# R613B.net
KiCad netlist of a schematic drawn in EAGLE
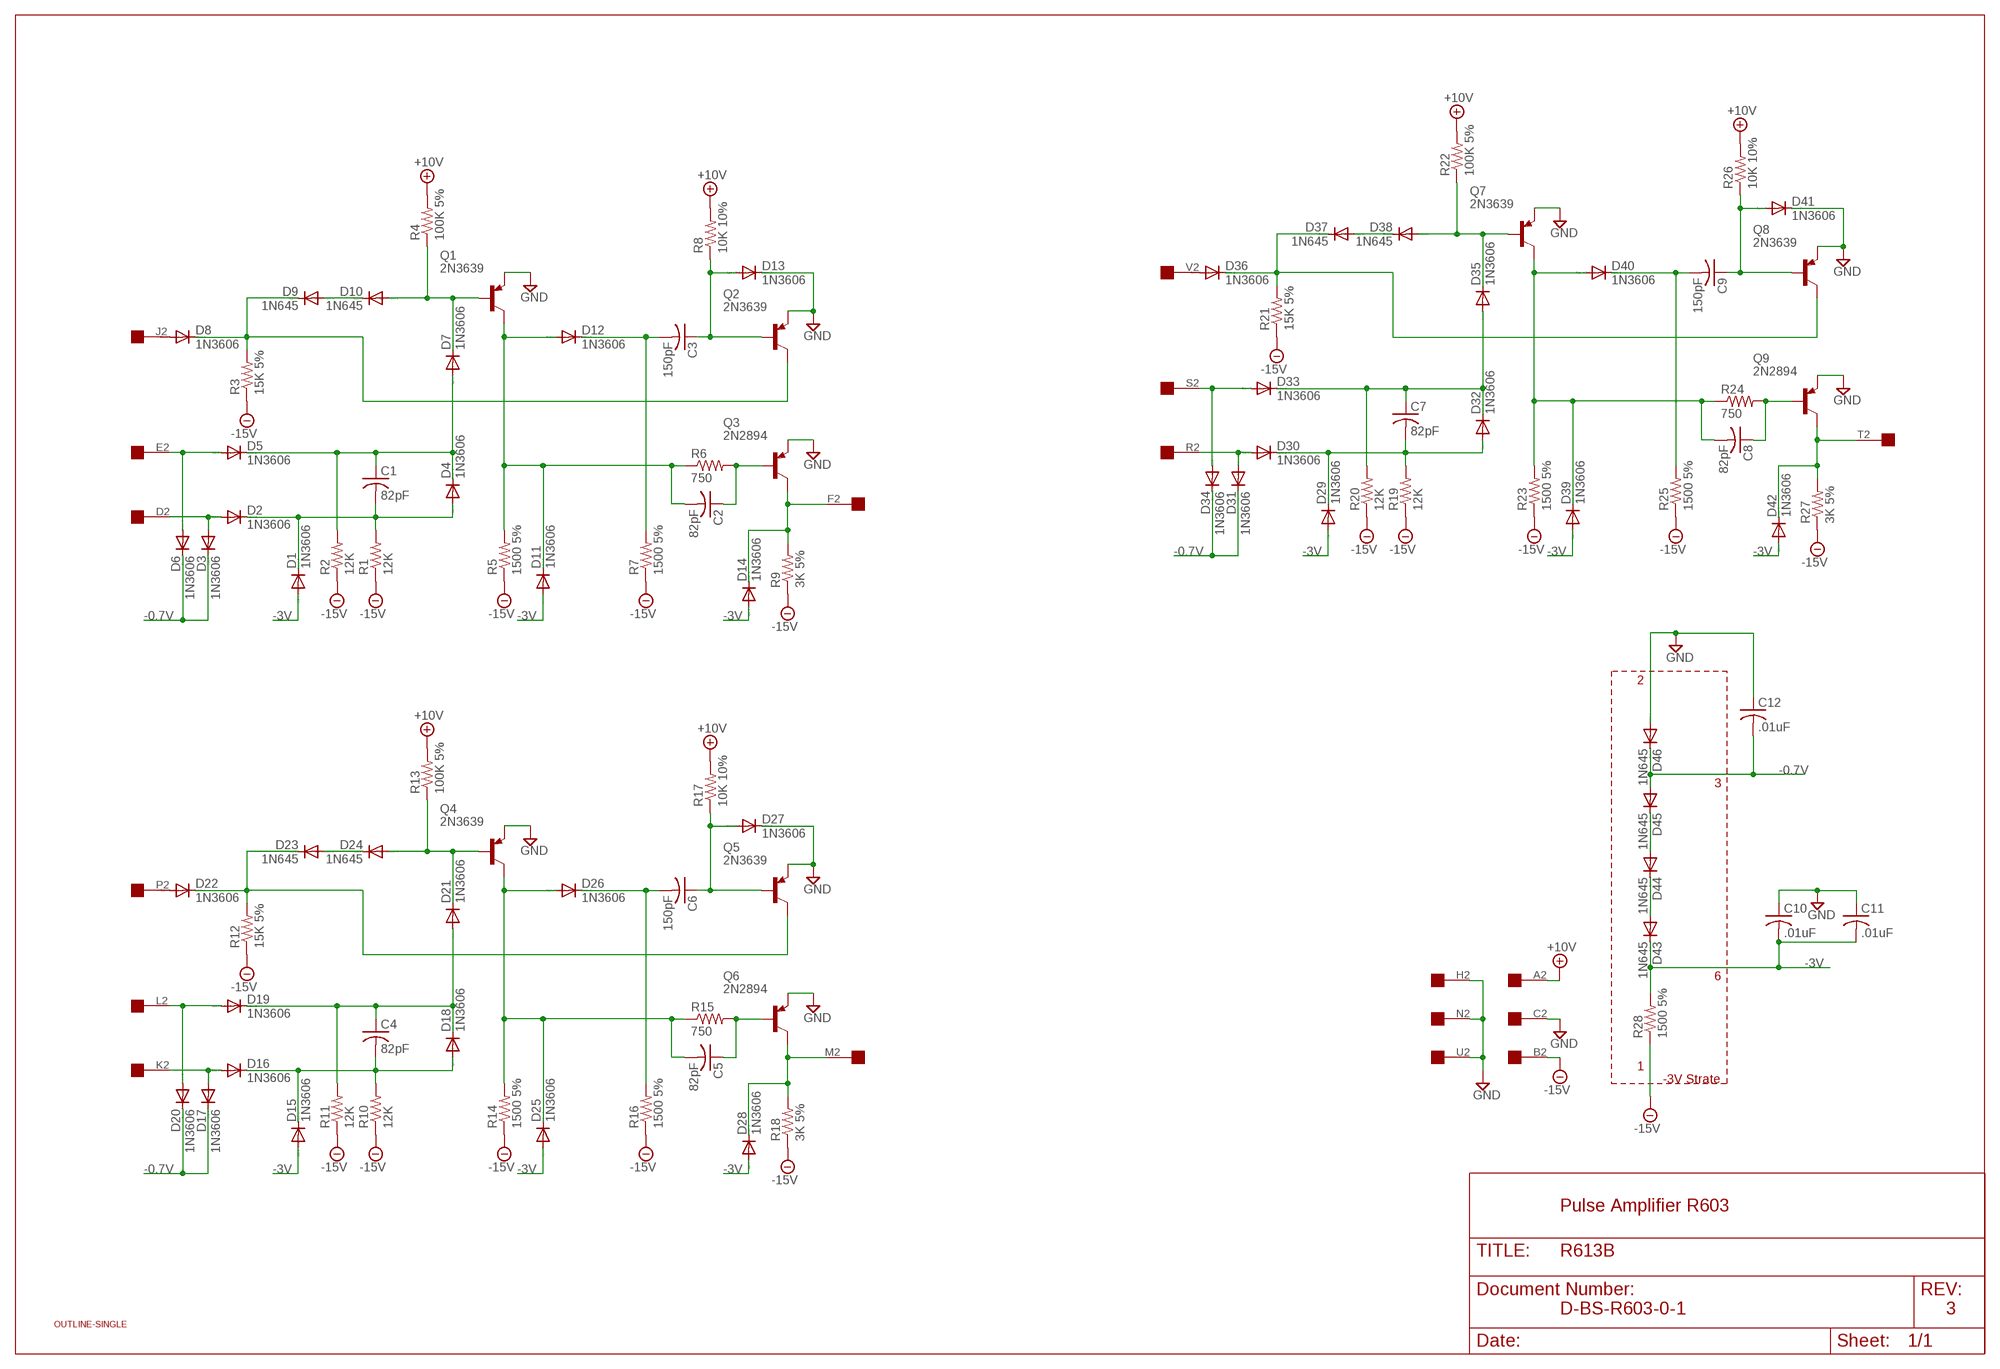
[diagram p0: schematic, sheet 1]

(export (version "E")
  (design (tool "Eeschema 10.0.6"))
  (components
    (comp (ref "C1")
      (value "82pF")
      (footprint "eagle-import:C050-025X075")
      (libsource (lib "eagle-import") (part "C-US050-025X075"))
    )
    (comp (ref "C2")
      (value "82pF")
      (footprint "eagle-import:C050-025X075")
      (libsource (lib "eagle-import") (part "C-US050-025X075"))
    )
    (comp (ref "C3")
      (value "150pF")
      (footprint "eagle-import:C050-025X075")
      (libsource (lib "eagle-import") (part "C-US050-025X075"))
    )
    (comp (ref "C4")
      (value "82pF")
      (footprint "eagle-import:C050-025X075")
      (libsource (lib "eagle-import") (part "C-US050-025X075"))
    )
    (comp (ref "C5")
      (value "82pF")
      (footprint "eagle-import:C050-025X075")
      (libsource (lib "eagle-import") (part "C-US050-025X075"))
    )
    (comp (ref "C6")
      (value "150pF")
      (footprint "eagle-import:C050-025X075")
      (libsource (lib "eagle-import") (part "C-US050-025X075"))
    )
    (comp (ref "C7")
      (value "82pF")
      (footprint "eagle-import:C050-025X075")
      (libsource (lib "eagle-import") (part "C-US050-025X075"))
    )
    (comp (ref "C8")
      (value "82pF")
      (footprint "eagle-import:C050-025X075")
      (libsource (lib "eagle-import") (part "C-US050-025X075"))
    )
    (comp (ref "C9")
      (value "150pF")
      (footprint "eagle-import:C050-025X075")
      (libsource (lib "eagle-import") (part "C-US050-025X075"))
    )
    (comp (ref "C10")
      (value ".01uF")
      (footprint "eagle-import:C050-025X075")
      (libsource (lib "eagle-import") (part "C-US050-025X075"))
    )
    (comp (ref "C11")
      (value ".01uF")
      (footprint "eagle-import:C050-025X075")
      (libsource (lib "eagle-import") (part "C-US050-025X075"))
    )
    (comp (ref "C12")
      (value ".01uF")
      (footprint "eagle-import:C050-025X075")
      (libsource (lib "eagle-import") (part "C-US050-025X075"))
    )
    (comp (ref "D1")
      (value "1N3606")
      (footprint "eagle-import:DO35-10")
      (libsource (lib "eagle-import") (part "1N4148DO35-10"))
    )
    (comp (ref "D2")
      (value "1N3606")
      (footprint "eagle-import:DO35-10")
      (libsource (lib "eagle-import") (part "1N4148DO35-10"))
    )
    (comp (ref "D3")
      (value "1N3606")
      (footprint "eagle-import:DO35-10")
      (libsource (lib "eagle-import") (part "1N4148DO35-10"))
    )
    (comp (ref "D4")
      (value "1N3606")
      (footprint "eagle-import:DO35-10")
      (libsource (lib "eagle-import") (part "1N4148DO35-10"))
    )
    (comp (ref "D5")
      (value "1N3606")
      (footprint "eagle-import:DO35-10")
      (libsource (lib "eagle-import") (part "1N4148DO35-10"))
    )
    (comp (ref "D6")
      (value "1N3606")
      (footprint "eagle-import:DO35-10")
      (libsource (lib "eagle-import") (part "1N4148DO35-10"))
    )
    (comp (ref "D7")
      (value "1N3606")
      (footprint "eagle-import:DO35-10")
      (libsource (lib "eagle-import") (part "1N4148DO35-10"))
    )
    (comp (ref "D8")
      (value "1N3606")
      (footprint "eagle-import:DO35-10")
      (libsource (lib "eagle-import") (part "1N4148DO35-10"))
    )
    (comp (ref "D9")
      (value "1N645")
      (footprint "eagle-import:DO35-10")
      (libsource (lib "eagle-import") (part "1N4148DO35-10"))
    )
    (comp (ref "D10")
      (value "1N645")
      (footprint "eagle-import:DO35-10")
      (libsource (lib "eagle-import") (part "1N4148DO35-10"))
    )
    (comp (ref "D11")
      (value "1N3606")
      (footprint "eagle-import:DO35-10")
      (libsource (lib "eagle-import") (part "1N4148DO35-10"))
    )
    (comp (ref "D12")
      (value "1N3606")
      (footprint "eagle-import:DO35-10")
      (libsource (lib "eagle-import") (part "1N4148DO35-10"))
    )
    (comp (ref "D13")
      (value "1N3606")
      (footprint "eagle-import:DO35-10")
      (libsource (lib "eagle-import") (part "1N4148DO35-10"))
    )
    (comp (ref "D14")
      (value "1N3606")
      (footprint "eagle-import:DO35-10")
      (libsource (lib "eagle-import") (part "1N4148DO35-10"))
    )
    (comp (ref "D15")
      (value "1N3606")
      (footprint "eagle-import:DO35-10")
      (libsource (lib "eagle-import") (part "1N4148DO35-10"))
    )
    (comp (ref "D16")
      (value "1N3606")
      (footprint "eagle-import:DO35-10")
      (libsource (lib "eagle-import") (part "1N4148DO35-10"))
    )
    (comp (ref "D17")
      (value "1N3606")
      (footprint "eagle-import:DO35-10")
      (libsource (lib "eagle-import") (part "1N4148DO35-10"))
    )
    (comp (ref "D18")
      (value "1N3606")
      (footprint "eagle-import:DO35-10")
      (libsource (lib "eagle-import") (part "1N4148DO35-10"))
    )
    (comp (ref "D19")
      (value "1N3606")
      (footprint "eagle-import:DO35-10")
      (libsource (lib "eagle-import") (part "1N4148DO35-10"))
    )
    (comp (ref "D20")
      (value "1N3606")
      (footprint "eagle-import:DO35-10")
      (libsource (lib "eagle-import") (part "1N4148DO35-10"))
    )
    (comp (ref "D21")
      (value "1N3606")
      (footprint "eagle-import:DO35-10")
      (libsource (lib "eagle-import") (part "1N4148DO35-10"))
    )
    (comp (ref "D22")
      (value "1N3606")
      (footprint "eagle-import:DO35-10")
      (libsource (lib "eagle-import") (part "1N4148DO35-10"))
    )
    (comp (ref "D23")
      (value "1N645")
      (footprint "eagle-import:DO35-10")
      (libsource (lib "eagle-import") (part "1N4148DO35-10"))
    )
    (comp (ref "D24")
      (value "1N645")
      (footprint "eagle-import:DO35-10")
      (libsource (lib "eagle-import") (part "1N4148DO35-10"))
    )
    (comp (ref "D25")
      (value "1N3606")
      (footprint "eagle-import:DO35-10")
      (libsource (lib "eagle-import") (part "1N4148DO35-10"))
    )
    (comp (ref "D26")
      (value "1N3606")
      (footprint "eagle-import:DO35-10")
      (libsource (lib "eagle-import") (part "1N4148DO35-10"))
    )
    (comp (ref "D27")
      (value "1N3606")
      (footprint "eagle-import:DO35-10")
      (libsource (lib "eagle-import") (part "1N4148DO35-10"))
    )
    (comp (ref "D28")
      (value "1N3606")
      (footprint "eagle-import:DO35-10")
      (libsource (lib "eagle-import") (part "1N4148DO35-10"))
    )
    (comp (ref "D29")
      (value "1N3606")
      (footprint "eagle-import:DO35-10")
      (libsource (lib "eagle-import") (part "1N4148DO35-10"))
    )
    (comp (ref "D30")
      (value "1N3606")
      (footprint "eagle-import:DO35-10")
      (libsource (lib "eagle-import") (part "1N4148DO35-10"))
    )
    (comp (ref "D31")
      (value "1N3606")
      (footprint "eagle-import:DO35-10")
      (libsource (lib "eagle-import") (part "1N4148DO35-10"))
    )
    (comp (ref "D32")
      (value "1N3606")
      (footprint "eagle-import:DO35-10")
      (libsource (lib "eagle-import") (part "1N4148DO35-10"))
    )
    (comp (ref "D33")
      (value "1N3606")
      (footprint "eagle-import:DO35-10")
      (libsource (lib "eagle-import") (part "1N4148DO35-10"))
    )
    (comp (ref "D34")
      (value "1N3606")
      (footprint "eagle-import:DO35-10")
      (libsource (lib "eagle-import") (part "1N4148DO35-10"))
    )
    (comp (ref "D35")
      (value "1N3606")
      (footprint "eagle-import:DO35-10")
      (libsource (lib "eagle-import") (part "1N4148DO35-10"))
    )
    (comp (ref "D36")
      (value "1N3606")
      (footprint "eagle-import:DO35-10")
      (libsource (lib "eagle-import") (part "1N4148DO35-10"))
    )
    (comp (ref "D37")
      (value "1N645")
      (footprint "eagle-import:DO35-10")
      (libsource (lib "eagle-import") (part "1N4148DO35-10"))
    )
    (comp (ref "D38")
      (value "1N645")
      (footprint "eagle-import:DO35-10")
      (libsource (lib "eagle-import") (part "1N4148DO35-10"))
    )
    (comp (ref "D39")
      (value "1N3606")
      (footprint "eagle-import:DO35-10")
      (libsource (lib "eagle-import") (part "1N4148DO35-10"))
    )
    (comp (ref "D40")
      (value "1N3606")
      (footprint "eagle-import:DO35-10")
      (libsource (lib "eagle-import") (part "1N4148DO35-10"))
    )
    (comp (ref "D41")
      (value "1N3606")
      (footprint "eagle-import:DO35-10")
      (libsource (lib "eagle-import") (part "1N4148DO35-10"))
    )
    (comp (ref "D42")
      (value "1N3606")
      (footprint "eagle-import:DO35-10")
      (libsource (lib "eagle-import") (part "1N4148DO35-10"))
    )
    (comp (ref "D43")
      (value "1N645")
      (footprint "eagle-import:DO35-10")
      (libsource (lib "eagle-import") (part "1N4148DO35-10"))
    )
    (comp (ref "D44")
      (value "1N645")
      (footprint "eagle-import:DO35-10")
      (libsource (lib "eagle-import") (part "1N4148DO35-10"))
    )
    (comp (ref "D45")
      (value "1N645")
      (footprint "eagle-import:DO35-10")
      (libsource (lib "eagle-import") (part "1N4148DO35-10"))
    )
    (comp (ref "D46")
      (value "1N645")
      (footprint "eagle-import:DO35-10")
      (libsource (lib "eagle-import") (part "1N4148DO35-10"))
    )
    (comp (ref "Q1")
      (value "2N3639")
      (footprint "eagle-import:TO39")
      (libsource (lib "eagle-import") (part "2N2904"))
    )
    (comp (ref "Q2")
      (value "2N3639")
      (footprint "eagle-import:TO39")
      (libsource (lib "eagle-import") (part "2N2904"))
    )
    (comp (ref "Q3")
      (value "2N2894")
      (footprint "eagle-import:TO39")
      (libsource (lib "eagle-import") (part "2N2904"))
    )
    (comp (ref "Q4")
      (value "2N3639")
      (footprint "eagle-import:TO39")
      (libsource (lib "eagle-import") (part "2N2904"))
    )
    (comp (ref "Q5")
      (value "2N3639")
      (footprint "eagle-import:TO39")
      (libsource (lib "eagle-import") (part "2N2904"))
    )
    (comp (ref "Q6")
      (value "2N2894")
      (footprint "eagle-import:TO39")
      (libsource (lib "eagle-import") (part "2N2904"))
    )
    (comp (ref "Q7")
      (value "2N3639")
      (footprint "eagle-import:TO39")
      (libsource (lib "eagle-import") (part "2N2904"))
    )
    (comp (ref "Q8")
      (value "2N3639")
      (footprint "eagle-import:TO39")
      (libsource (lib "eagle-import") (part "2N2904"))
    )
    (comp (ref "Q9")
      (value "2N2894")
      (footprint "eagle-import:TO39")
      (libsource (lib "eagle-import") (part "2N2904"))
    )
    (comp (ref "R1")
      (value "12K")
      (footprint "eagle-import:0207_10")
      (libsource (lib "eagle-import") (part "R-US_0207/10"))
    )
    (comp (ref "R2")
      (value "12K")
      (footprint "eagle-import:0207_10")
      (libsource (lib "eagle-import") (part "R-US_0207/10"))
    )
    (comp (ref "R3")
      (value "15K 5%")
      (footprint "eagle-import:0207_10")
      (libsource (lib "eagle-import") (part "R-US_0207/10"))
    )
    (comp (ref "R4")
      (value "100K 5%")
      (footprint "eagle-import:0207_10")
      (libsource (lib "eagle-import") (part "R-US_0207/10"))
    )
    (comp (ref "R5")
      (value "1500 5%")
      (footprint "eagle-import:0207_10")
      (libsource (lib "eagle-import") (part "R-US_0207/10"))
    )
    (comp (ref "R6")
      (value "750")
      (footprint "eagle-import:0207_10")
      (libsource (lib "eagle-import") (part "R-US_0207/10"))
    )
    (comp (ref "R7")
      (value "1500 5%")
      (footprint "eagle-import:0207_10")
      (libsource (lib "eagle-import") (part "R-US_0207/10"))
    )
    (comp (ref "R8")
      (value "10K 10%")
      (footprint "eagle-import:0207_10")
      (libsource (lib "eagle-import") (part "R-US_0207/10"))
    )
    (comp (ref "R9")
      (value "3K 5%")
      (footprint "eagle-import:0207_10")
      (libsource (lib "eagle-import") (part "R-US_0207/10"))
    )
    (comp (ref "R10")
      (value "12K")
      (footprint "eagle-import:0207_10")
      (libsource (lib "eagle-import") (part "R-US_0207/10"))
    )
    (comp (ref "R11")
      (value "12K")
      (footprint "eagle-import:0207_10")
      (libsource (lib "eagle-import") (part "R-US_0207/10"))
    )
    (comp (ref "R12")
      (value "15K 5%")
      (footprint "eagle-import:0207_10")
      (libsource (lib "eagle-import") (part "R-US_0207/10"))
    )
    (comp (ref "R13")
      (value "100K 5%")
      (footprint "eagle-import:0207_10")
      (libsource (lib "eagle-import") (part "R-US_0207/10"))
    )
    (comp (ref "R14")
      (value "1500 5%")
      (footprint "eagle-import:0207_10")
      (libsource (lib "eagle-import") (part "R-US_0207/10"))
    )
    (comp (ref "R15")
      (value "750")
      (footprint "eagle-import:0207_10")
      (libsource (lib "eagle-import") (part "R-US_0207/10"))
    )
    (comp (ref "R16")
      (value "1500 5%")
      (footprint "eagle-import:0207_10")
      (libsource (lib "eagle-import") (part "R-US_0207/10"))
    )
    (comp (ref "R17")
      (value "10K 10%")
      (footprint "eagle-import:0207_10")
      (libsource (lib "eagle-import") (part "R-US_0207/10"))
    )
    (comp (ref "R18")
      (value "3K 5%")
      (footprint "eagle-import:0207_10")
      (libsource (lib "eagle-import") (part "R-US_0207/10"))
    )
    (comp (ref "R19")
      (value "12K")
      (footprint "eagle-import:0207_10")
      (libsource (lib "eagle-import") (part "R-US_0207/10"))
    )
    (comp (ref "R20")
      (value "12K")
      (footprint "eagle-import:0207_10")
      (libsource (lib "eagle-import") (part "R-US_0207/10"))
    )
    (comp (ref "R21")
      (value "15K 5%")
      (footprint "eagle-import:0207_10")
      (libsource (lib "eagle-import") (part "R-US_0207/10"))
    )
    (comp (ref "R22")
      (value "100K 5%")
      (footprint "eagle-import:0207_10")
      (libsource (lib "eagle-import") (part "R-US_0207/10"))
    )
    (comp (ref "R23")
      (value "1500 5%")
      (footprint "eagle-import:0207_10")
      (libsource (lib "eagle-import") (part "R-US_0207/10"))
    )
    (comp (ref "R24")
      (value "750")
      (footprint "eagle-import:0207_10")
      (libsource (lib "eagle-import") (part "R-US_0207/10"))
    )
    (comp (ref "R25")
      (value "1500 5%")
      (footprint "eagle-import:0207_10")
      (libsource (lib "eagle-import") (part "R-US_0207/10"))
    )
    (comp (ref "R26")
      (value "10K 10%")
      (footprint "eagle-import:0207_10")
      (libsource (lib "eagle-import") (part "R-US_0207/10"))
    )
    (comp (ref "R27")
      (value "3K 5%")
      (footprint "eagle-import:0207_10")
      (libsource (lib "eagle-import") (part "R-US_0207/10"))
    )
    (comp (ref "R28")
      (value "1500 5%")
      (footprint "eagle-import:0207_10")
      (libsource (lib "eagle-import") (part "R-US_0207/10"))
    )
    (comp (ref "U$1")
      (value "OUTLINE-SINGLE")
      (footprint "eagle-import:SINGLE")
      (libsource (lib "eagle-import") (part "OUTLINE-SINGLE"))
    )
    (comp (ref "U$2")
      (value "EDGE-1")
      (footprint "eagle-import:EDGE-CON1")
      (libsource (lib "eagle-import") (part "EDGE-1"))
    )
  )
  (nets
    (net (code "1") (name "+10V") (class "Default")
      (node (ref "R13") (pin "2") (pinfunction "2_2") (pintype "passive"))
      (node (ref "R17") (pin "2") (pinfunction "2_2") (pintype "passive"))
      (node (ref "R22") (pin "2") (pinfunction "2_2") (pintype "passive"))
      (node (ref "R26") (pin "2") (pinfunction "2_2") (pintype "passive"))
      (node (ref "R4") (pin "2") (pinfunction "2_2") (pintype "passive"))
      (node (ref "R8") (pin "2") (pinfunction "2_2") (pintype "passive"))
      (node (ref "U$2") (pin "A2") (pinfunction "1_A2") (pintype "bidirectional"))
    )
    (net (code "2") (name "-15V") (class "Default")
      (node (ref "R1") (pin "1") (pinfunction "1_1") (pintype "passive"))
      (node (ref "R10") (pin "1") (pinfunction "1_1") (pintype "passive"))
      (node (ref "R11") (pin "1") (pinfunction "1_1") (pintype "passive"))
      (node (ref "R12") (pin "1") (pinfunction "1_1") (pintype "passive"))
      (node (ref "R14") (pin "1") (pinfunction "1_1") (pintype "passive"))
      (node (ref "R16") (pin "1") (pinfunction "1_1") (pintype "passive"))
      (node (ref "R18") (pin "1") (pinfunction "1_1") (pintype "passive"))
      (node (ref "R19") (pin "1") (pinfunction "1_1") (pintype "passive"))
      (node (ref "R2") (pin "1") (pinfunction "1_1") (pintype "passive"))
      (node (ref "R20") (pin "1") (pinfunction "1_1") (pintype "passive"))
      (node (ref "R21") (pin "1") (pinfunction "1_1") (pintype "passive"))
      (node (ref "R23") (pin "1") (pinfunction "1_1") (pintype "passive"))
      (node (ref "R25") (pin "1") (pinfunction "1_1") (pintype "passive"))
      (node (ref "R27") (pin "1") (pinfunction "1_1") (pintype "passive"))
      (node (ref "R28") (pin "1") (pinfunction "1_1") (pintype "passive"))
      (node (ref "R3") (pin "1") (pinfunction "1_1") (pintype "passive"))
      (node (ref "R5") (pin "1") (pinfunction "1_1") (pintype "passive"))
      (node (ref "R7") (pin "1") (pinfunction "1_1") (pintype "passive"))
      (node (ref "R9") (pin "1") (pinfunction "1_1") (pintype "passive"))
      (node (ref "U$2") (pin "B2") (pinfunction "1_B2") (pintype "bidirectional"))
    )
    (net (code "3") (name "/-0.7V") (class "Default")
      (node (ref "C12") (pin "2") (pinfunction "2_2") (pintype "passive"))
      (node (ref "D17") (pin "C") (pinfunction "C_C") (pintype "passive"))
      (node (ref "D20") (pin "C") (pinfunction "C_C") (pintype "passive"))
      (node (ref "D3") (pin "C") (pinfunction "C_C") (pintype "passive"))
      (node (ref "D31") (pin "C") (pinfunction "C_C") (pintype "passive"))
      (node (ref "D34") (pin "C") (pinfunction "C_C") (pintype "passive"))
      (node (ref "D45") (pin "A") (pinfunction "A_A") (pintype "passive"))
      (node (ref "D46") (pin "C") (pinfunction "C_C") (pintype "passive"))
      (node (ref "D6") (pin "C") (pinfunction "C_C") (pintype "passive"))
    )
    (net (code "4") (name "/-3V") (class "Default")
      (node (ref "C10") (pin "2") (pinfunction "2_2") (pintype "passive"))
      (node (ref "C11") (pin "2") (pinfunction "2_2") (pintype "passive"))
      (node (ref "D1") (pin "A") (pinfunction "A_A") (pintype "passive"))
      (node (ref "D11") (pin "A") (pinfunction "A_A") (pintype "passive"))
      (node (ref "D14") (pin "A") (pinfunction "A_A") (pintype "passive"))
      (node (ref "D15") (pin "A") (pinfunction "A_A") (pintype "passive"))
      (node (ref "D25") (pin "A") (pinfunction "A_A") (pintype "passive"))
      (node (ref "D28") (pin "A") (pinfunction "A_A") (pintype "passive"))
      (node (ref "D29") (pin "A") (pinfunction "A_A") (pintype "passive"))
      (node (ref "D39") (pin "A") (pinfunction "A_A") (pintype "passive"))
      (node (ref "D42") (pin "A") (pinfunction "A_A") (pintype "passive"))
      (node (ref "D43") (pin "C") (pinfunction "C_C") (pintype "passive"))
      (node (ref "R28") (pin "2") (pinfunction "2_2") (pintype "passive"))
    )
    (net (code "5") (name "GND") (class "Default")
      (node (ref "C10") (pin "1") (pinfunction "1_1") (pintype "passive"))
      (node (ref "C11") (pin "1") (pinfunction "1_1") (pintype "passive"))
      (node (ref "C12") (pin "1") (pinfunction "1_1") (pintype "passive"))
      (node (ref "D13") (pin "C") (pinfunction "C_C") (pintype "passive"))
      (node (ref "D27") (pin "C") (pinfunction "C_C") (pintype "passive"))
      (node (ref "D41") (pin "C") (pinfunction "C_C") (pintype "passive"))
      (node (ref "D46") (pin "A") (pinfunction "A_A") (pintype "passive"))
      (node (ref "Q1") (pin "1") (pinfunction "E_1") (pintype "passive"))
      (node (ref "Q2") (pin "1") (pinfunction "E_1") (pintype "passive"))
      (node (ref "Q3") (pin "1") (pinfunction "E_1") (pintype "passive"))
      (node (ref "Q4") (pin "1") (pinfunction "E_1") (pintype "passive"))
      (node (ref "Q5") (pin "1") (pinfunction "E_1") (pintype "passive"))
      (node (ref "Q6") (pin "1") (pinfunction "E_1") (pintype "passive"))
      (node (ref "Q7") (pin "1") (pinfunction "E_1") (pintype "passive"))
      (node (ref "Q8") (pin "1") (pinfunction "E_1") (pintype "passive"))
      (node (ref "Q9") (pin "1") (pinfunction "E_1") (pintype "passive"))
      (node (ref "U$2") (pin "C2") (pinfunction "1_C2") (pintype "bidirectional"))
      (node (ref "U$2") (pin "H2") (pinfunction "1_H2") (pintype "bidirectional"))
      (node (ref "U$2") (pin "N2") (pinfunction "1_N2") (pintype "bidirectional"))
      (node (ref "U$2") (pin "U2") (pinfunction "1_U2") (pintype "bidirectional"))
    )
    (net (code "6") (name "Net-(C1-Pad1)") (class "Default")
      (node (ref "C1") (pin "1") (pinfunction "1_1") (pintype "passive"))
      (node (ref "D4") (pin "C") (pinfunction "C_C") (pintype "passive"))
      (node (ref "D5") (pin "C") (pinfunction "C_C") (pintype "passive"))
      (node (ref "D7") (pin "A") (pinfunction "A_A") (pintype "passive"))
      (node (ref "R2") (pin "2") (pinfunction "2_2") (pintype "passive"))
    )
    (net (code "7") (name "Net-(C1-Pad2)") (class "Default")
      (node (ref "C1") (pin "2") (pinfunction "2_2") (pintype "passive"))
      (node (ref "D1") (pin "C") (pinfunction "C_C") (pintype "passive"))
      (node (ref "D2") (pin "C") (pinfunction "C_C") (pintype "passive"))
      (node (ref "D4") (pin "A") (pinfunction "A_A") (pintype "passive"))
      (node (ref "R1") (pin "2") (pinfunction "2_2") (pintype "passive"))
    )
    (net (code "8") (name "Net-(C3-Pad2)") (class "Default")
      (node (ref "C3") (pin "2") (pinfunction "2_2") (pintype "passive"))
      (node (ref "D12") (pin "C") (pinfunction "C_C") (pintype "passive"))
      (node (ref "R7") (pin "2") (pinfunction "2_2") (pintype "passive"))
    )
    (net (code "9") (name "Net-(C4-Pad1)") (class "Default")
      (node (ref "C4") (pin "1") (pinfunction "1_1") (pintype "passive"))
      (node (ref "D18") (pin "C") (pinfunction "C_C") (pintype "passive"))
      (node (ref "D19") (pin "C") (pinfunction "C_C") (pintype "passive"))
      (node (ref "D21") (pin "A") (pinfunction "A_A") (pintype "passive"))
      (node (ref "R11") (pin "2") (pinfunction "2_2") (pintype "passive"))
    )
    (net (code "10") (name "Net-(C4-Pad2)") (class "Default")
      (node (ref "C4") (pin "2") (pinfunction "2_2") (pintype "passive"))
      (node (ref "D15") (pin "C") (pinfunction "C_C") (pintype "passive"))
      (node (ref "D16") (pin "C") (pinfunction "C_C") (pintype "passive"))
      (node (ref "D18") (pin "A") (pinfunction "A_A") (pintype "passive"))
      (node (ref "R10") (pin "2") (pinfunction "2_2") (pintype "passive"))
    )
    (net (code "11") (name "Net-(C6-Pad2)") (class "Default")
      (node (ref "C6") (pin "2") (pinfunction "2_2") (pintype "passive"))
      (node (ref "D26") (pin "C") (pinfunction "C_C") (pintype "passive"))
      (node (ref "R16") (pin "2") (pinfunction "2_2") (pintype "passive"))
    )
    (net (code "12") (name "Net-(C7-Pad1)") (class "Default")
      (node (ref "C7") (pin "1") (pinfunction "1_1") (pintype "passive"))
      (node (ref "D32") (pin "C") (pinfunction "C_C") (pintype "passive"))
      (node (ref "D33") (pin "C") (pinfunction "C_C") (pintype "passive"))
      (node (ref "D35") (pin "A") (pinfunction "A_A") (pintype "passive"))
      (node (ref "R20") (pin "2") (pinfunction "2_2") (pintype "passive"))
    )
    (net (code "13") (name "Net-(C7-Pad2)") (class "Default")
      (node (ref "C7") (pin "2") (pinfunction "2_2") (pintype "passive"))
      (node (ref "D29") (pin "C") (pinfunction "C_C") (pintype "passive"))
      (node (ref "D30") (pin "C") (pinfunction "C_C") (pintype "passive"))
      (node (ref "D32") (pin "A") (pinfunction "A_A") (pintype "passive"))
      (node (ref "R19") (pin "2") (pinfunction "2_2") (pintype "passive"))
    )
    (net (code "14") (name "Net-(C9-Pad2)") (class "Default")
      (node (ref "C9") (pin "2") (pinfunction "2_2") (pintype "passive"))
      (node (ref "D40") (pin "C") (pinfunction "C_C") (pintype "passive"))
      (node (ref "R25") (pin "2") (pinfunction "2_2") (pintype "passive"))
    )
    (net (code "15") (name "Net-(D10-PadC)") (class "Default")
      (node (ref "D10") (pin "C") (pinfunction "C_C") (pintype "passive"))
      (node (ref "D9") (pin "A") (pinfunction "A_A") (pintype "passive"))
    )
    (net (code "16") (name "Net-(D23-PadA)") (class "Default")
      (node (ref "D23") (pin "A") (pinfunction "A_A") (pintype "passive"))
      (node (ref "D24") (pin "C") (pinfunction "C_C") (pintype "passive"))
    )
    (net (code "17") (name "Net-(D37-PadA)") (class "Default")
      (node (ref "D37") (pin "A") (pinfunction "A_A") (pintype "passive"))
      (node (ref "D38") (pin "C") (pinfunction "C_C") (pintype "passive"))
    )
    (net (code "18") (name "Net-(D43-PadA)") (class "Default")
      (node (ref "D43") (pin "A") (pinfunction "A_A") (pintype "passive"))
      (node (ref "D44") (pin "C") (pinfunction "C_C") (pintype "passive"))
    )
    (net (code "19") (name "Net-(D44-PadA)") (class "Default")
      (node (ref "D44") (pin "A") (pinfunction "A_A") (pintype "passive"))
      (node (ref "D45") (pin "C") (pinfunction "C_C") (pintype "passive"))
    )
    (net (code "20") (name "Net-(Q1-B)") (class "Default")
      (node (ref "D10") (pin "A") (pinfunction "A_A") (pintype "passive"))
      (node (ref "D7") (pin "C") (pinfunction "C_C") (pintype "passive"))
      (node (ref "Q1") (pin "2") (pinfunction "B_2") (pintype "passive"))
      (node (ref "R4") (pin "1") (pinfunction "1_1") (pintype "passive"))
    )
    (net (code "21") (name "Net-(Q1-C)") (class "Default")
      (node (ref "C2") (pin "2") (pinfunction "2_2") (pintype "passive"))
      (node (ref "D11") (pin "C") (pinfunction "C_C") (pintype "passive"))
      (node (ref "D12") (pin "A") (pinfunction "A_A") (pintype "passive"))
      (node (ref "Q1") (pin "3") (pinfunction "C_3") (pintype "passive"))
      (node (ref "R5") (pin "2") (pinfunction "2_2") (pintype "passive"))
      (node (ref "R6") (pin "1") (pinfunction "1_1") (pintype "passive"))
    )
    (net (code "22") (name "Net-(Q2-B)") (class "Default")
      (node (ref "C3") (pin "1") (pinfunction "1_1") (pintype "passive"))
      (node (ref "D13") (pin "A") (pinfunction "A_A") (pintype "passive"))
      (node (ref "Q2") (pin "2") (pinfunction "B_2") (pintype "passive"))
      (node (ref "R8") (pin "1") (pinfunction "1_1") (pintype "passive"))
    )
    (net (code "23") (name "Net-(Q2-C)") (class "Default")
      (node (ref "D8") (pin "C") (pinfunction "C_C") (pintype "passive"))
      (node (ref "D9") (pin "C") (pinfunction "C_C") (pintype "passive"))
      (node (ref "Q2") (pin "3") (pinfunction "C_3") (pintype "passive"))
      (node (ref "R3") (pin "2") (pinfunction "2_2") (pintype "passive"))
    )
    (net (code "24") (name "Net-(Q3-B)") (class "Default")
      (node (ref "C2") (pin "1") (pinfunction "1_1") (pintype "passive"))
      (node (ref "Q3") (pin "2") (pinfunction "B_2") (pintype "passive"))
      (node (ref "R6") (pin "2") (pinfunction "2_2") (pintype "passive"))
    )
    (net (code "25") (name "Net-(Q3-C)") (class "Default")
      (node (ref "D14") (pin "C") (pinfunction "C_C") (pintype "passive"))
      (node (ref "Q3") (pin "3") (pinfunction "C_3") (pintype "passive"))
      (node (ref "R9") (pin "2") (pinfunction "2_2") (pintype "passive"))
      (node (ref "U$2") (pin "F2") (pinfunction "1_F2") (pintype "bidirectional"))
    )
    (net (code "26") (name "Net-(Q4-B)") (class "Default")
      (node (ref "D21") (pin "C") (pinfunction "C_C") (pintype "passive"))
      (node (ref "D24") (pin "A") (pinfunction "A_A") (pintype "passive"))
      (node (ref "Q4") (pin "2") (pinfunction "B_2") (pintype "passive"))
      (node (ref "R13") (pin "1") (pinfunction "1_1") (pintype "passive"))
    )
    (net (code "27") (name "Net-(Q4-C)") (class "Default")
      (node (ref "C5") (pin "2") (pinfunction "2_2") (pintype "passive"))
      (node (ref "D25") (pin "C") (pinfunction "C_C") (pintype "passive"))
      (node (ref "D26") (pin "A") (pinfunction "A_A") (pintype "passive"))
      (node (ref "Q4") (pin "3") (pinfunction "C_3") (pintype "passive"))
      (node (ref "R14") (pin "2") (pinfunction "2_2") (pintype "passive"))
      (node (ref "R15") (pin "1") (pinfunction "1_1") (pintype "passive"))
    )
    (net (code "28") (name "Net-(Q5-B)") (class "Default")
      (node (ref "C6") (pin "1") (pinfunction "1_1") (pintype "passive"))
      (node (ref "D27") (pin "A") (pinfunction "A_A") (pintype "passive"))
      (node (ref "Q5") (pin "2") (pinfunction "B_2") (pintype "passive"))
      (node (ref "R17") (pin "1") (pinfunction "1_1") (pintype "passive"))
    )
    (net (code "29") (name "Net-(Q5-C)") (class "Default")
      (node (ref "D22") (pin "C") (pinfunction "C_C") (pintype "passive"))
      (node (ref "D23") (pin "C") (pinfunction "C_C") (pintype "passive"))
      (node (ref "Q5") (pin "3") (pinfunction "C_3") (pintype "passive"))
      (node (ref "R12") (pin "2") (pinfunction "2_2") (pintype "passive"))
    )
    (net (code "30") (name "Net-(Q6-B)") (class "Default")
      (node (ref "C5") (pin "1") (pinfunction "1_1") (pintype "passive"))
      (node (ref "Q6") (pin "2") (pinfunction "B_2") (pintype "passive"))
      (node (ref "R15") (pin "2") (pinfunction "2_2") (pintype "passive"))
    )
    (net (code "31") (name "Net-(Q6-C)") (class "Default")
      (node (ref "D28") (pin "C") (pinfunction "C_C") (pintype "passive"))
      (node (ref "Q6") (pin "3") (pinfunction "C_3") (pintype "passive"))
      (node (ref "R18") (pin "2") (pinfunction "2_2") (pintype "passive"))
      (node (ref "U$2") (pin "M2") (pinfunction "1_M2") (pintype "bidirectional"))
    )
    (net (code "32") (name "Net-(Q7-B)") (class "Default")
      (node (ref "D35") (pin "C") (pinfunction "C_C") (pintype "passive"))
      (node (ref "D38") (pin "A") (pinfunction "A_A") (pintype "passive"))
      (node (ref "Q7") (pin "2") (pinfunction "B_2") (pintype "passive"))
      (node (ref "R22") (pin "1") (pinfunction "1_1") (pintype "passive"))
    )
    (net (code "33") (name "Net-(Q7-C)") (class "Default")
      (node (ref "C8") (pin "2") (pinfunction "2_2") (pintype "passive"))
      (node (ref "D39") (pin "C") (pinfunction "C_C") (pintype "passive"))
      (node (ref "D40") (pin "A") (pinfunction "A_A") (pintype "passive"))
      (node (ref "Q7") (pin "3") (pinfunction "C_3") (pintype "passive"))
      (node (ref "R23") (pin "2") (pinfunction "2_2") (pintype "passive"))
      (node (ref "R24") (pin "1") (pinfunction "1_1") (pintype "passive"))
    )
    (net (code "34") (name "Net-(Q8-B)") (class "Default")
      (node (ref "C9") (pin "1") (pinfunction "1_1") (pintype "passive"))
      (node (ref "D41") (pin "A") (pinfunction "A_A") (pintype "passive"))
      (node (ref "Q8") (pin "2") (pinfunction "B_2") (pintype "passive"))
      (node (ref "R26") (pin "1") (pinfunction "1_1") (pintype "passive"))
    )
    (net (code "35") (name "Net-(Q8-C)") (class "Default")
      (node (ref "D36") (pin "C") (pinfunction "C_C") (pintype "passive"))
      (node (ref "D37") (pin "C") (pinfunction "C_C") (pintype "passive"))
      (node (ref "Q8") (pin "3") (pinfunction "C_3") (pintype "passive"))
      (node (ref "R21") (pin "2") (pinfunction "2_2") (pintype "passive"))
    )
    (net (code "36") (name "Net-(Q9-B)") (class "Default")
      (node (ref "C8") (pin "1") (pinfunction "1_1") (pintype "passive"))
      (node (ref "Q9") (pin "2") (pinfunction "B_2") (pintype "passive"))
      (node (ref "R24") (pin "2") (pinfunction "2_2") (pintype "passive"))
    )
    (net (code "37") (name "Net-(Q9-C)") (class "Default")
      (node (ref "D42") (pin "C") (pinfunction "C_C") (pintype "passive"))
      (node (ref "Q9") (pin "3") (pinfunction "C_3") (pintype "passive"))
      (node (ref "R27") (pin "2") (pinfunction "2_2") (pintype "passive"))
      (node (ref "U$2") (pin "T2") (pinfunction "1_T2") (pintype "bidirectional"))
    )
    (net (code "38") (name "Net-(U$2D-1)") (class "Default")
      (node (ref "D2") (pin "A") (pinfunction "A_A") (pintype "passive"))
      (node (ref "D3") (pin "A") (pinfunction "A_A") (pintype "passive"))
      (node (ref "U$2") (pin "D2") (pinfunction "1_D2") (pintype "bidirectional"))
    )
    (net (code "39") (name "Net-(U$2E-1)") (class "Default")
      (node (ref "D5") (pin "A") (pinfunction "A_A") (pintype "passive"))
      (node (ref "D6") (pin "A") (pinfunction "A_A") (pintype "passive"))
      (node (ref "U$2") (pin "E2") (pinfunction "1_E2") (pintype "bidirectional"))
    )
    (net (code "40") (name "Net-(U$2H-1)") (class "Default")
      (node (ref "D8") (pin "A") (pinfunction "A_A") (pintype "passive"))
      (node (ref "U$2") (pin "J2") (pinfunction "1_J2") (pintype "bidirectional"))
    )
    (net (code "41") (name "Net-(U$2I-1)") (class "Default")
      (node (ref "D16") (pin "A") (pinfunction "A_A") (pintype "passive"))
      (node (ref "D17") (pin "A") (pinfunction "A_A") (pintype "passive"))
      (node (ref "U$2") (pin "K2") (pinfunction "1_K2") (pintype "bidirectional"))
    )
    (net (code "42") (name "Net-(U$2J-1)") (class "Default")
      (node (ref "D19") (pin "A") (pinfunction "A_A") (pintype "passive"))
      (node (ref "D20") (pin "A") (pinfunction "A_A") (pintype "passive"))
      (node (ref "U$2") (pin "L2") (pinfunction "1_L2") (pintype "bidirectional"))
    )
    (net (code "43") (name "Net-(U$2M-1)") (class "Default")
      (node (ref "D22") (pin "A") (pinfunction "A_A") (pintype "passive"))
      (node (ref "U$2") (pin "P2") (pinfunction "1_P2") (pintype "bidirectional"))
    )
    (net (code "44") (name "Net-(U$2N-1)") (class "Default")
      (node (ref "D30") (pin "A") (pinfunction "A_A") (pintype "passive"))
      (node (ref "D31") (pin "A") (pinfunction "A_A") (pintype "passive"))
      (node (ref "U$2") (pin "R2") (pinfunction "1_R2") (pintype "bidirectional"))
    )
    (net (code "45") (name "Net-(U$2O-1)") (class "Default")
      (node (ref "D33") (pin "A") (pinfunction "A_A") (pintype "passive"))
      (node (ref "D34") (pin "A") (pinfunction "A_A") (pintype "passive"))
      (node (ref "U$2") (pin "S2") (pinfunction "1_S2") (pintype "bidirectional"))
    )
    (net (code "46") (name "Net-(U$2R-1)") (class "Default")
      (node (ref "D36") (pin "A") (pinfunction "A_A") (pintype "passive"))
      (node (ref "U$2") (pin "V2") (pinfunction "1_V2") (pintype "bidirectional"))
    )
  )
)
